# TUSB4041_PINOUT.net
KiCad netlist of a schematic drawn in Altium Designer
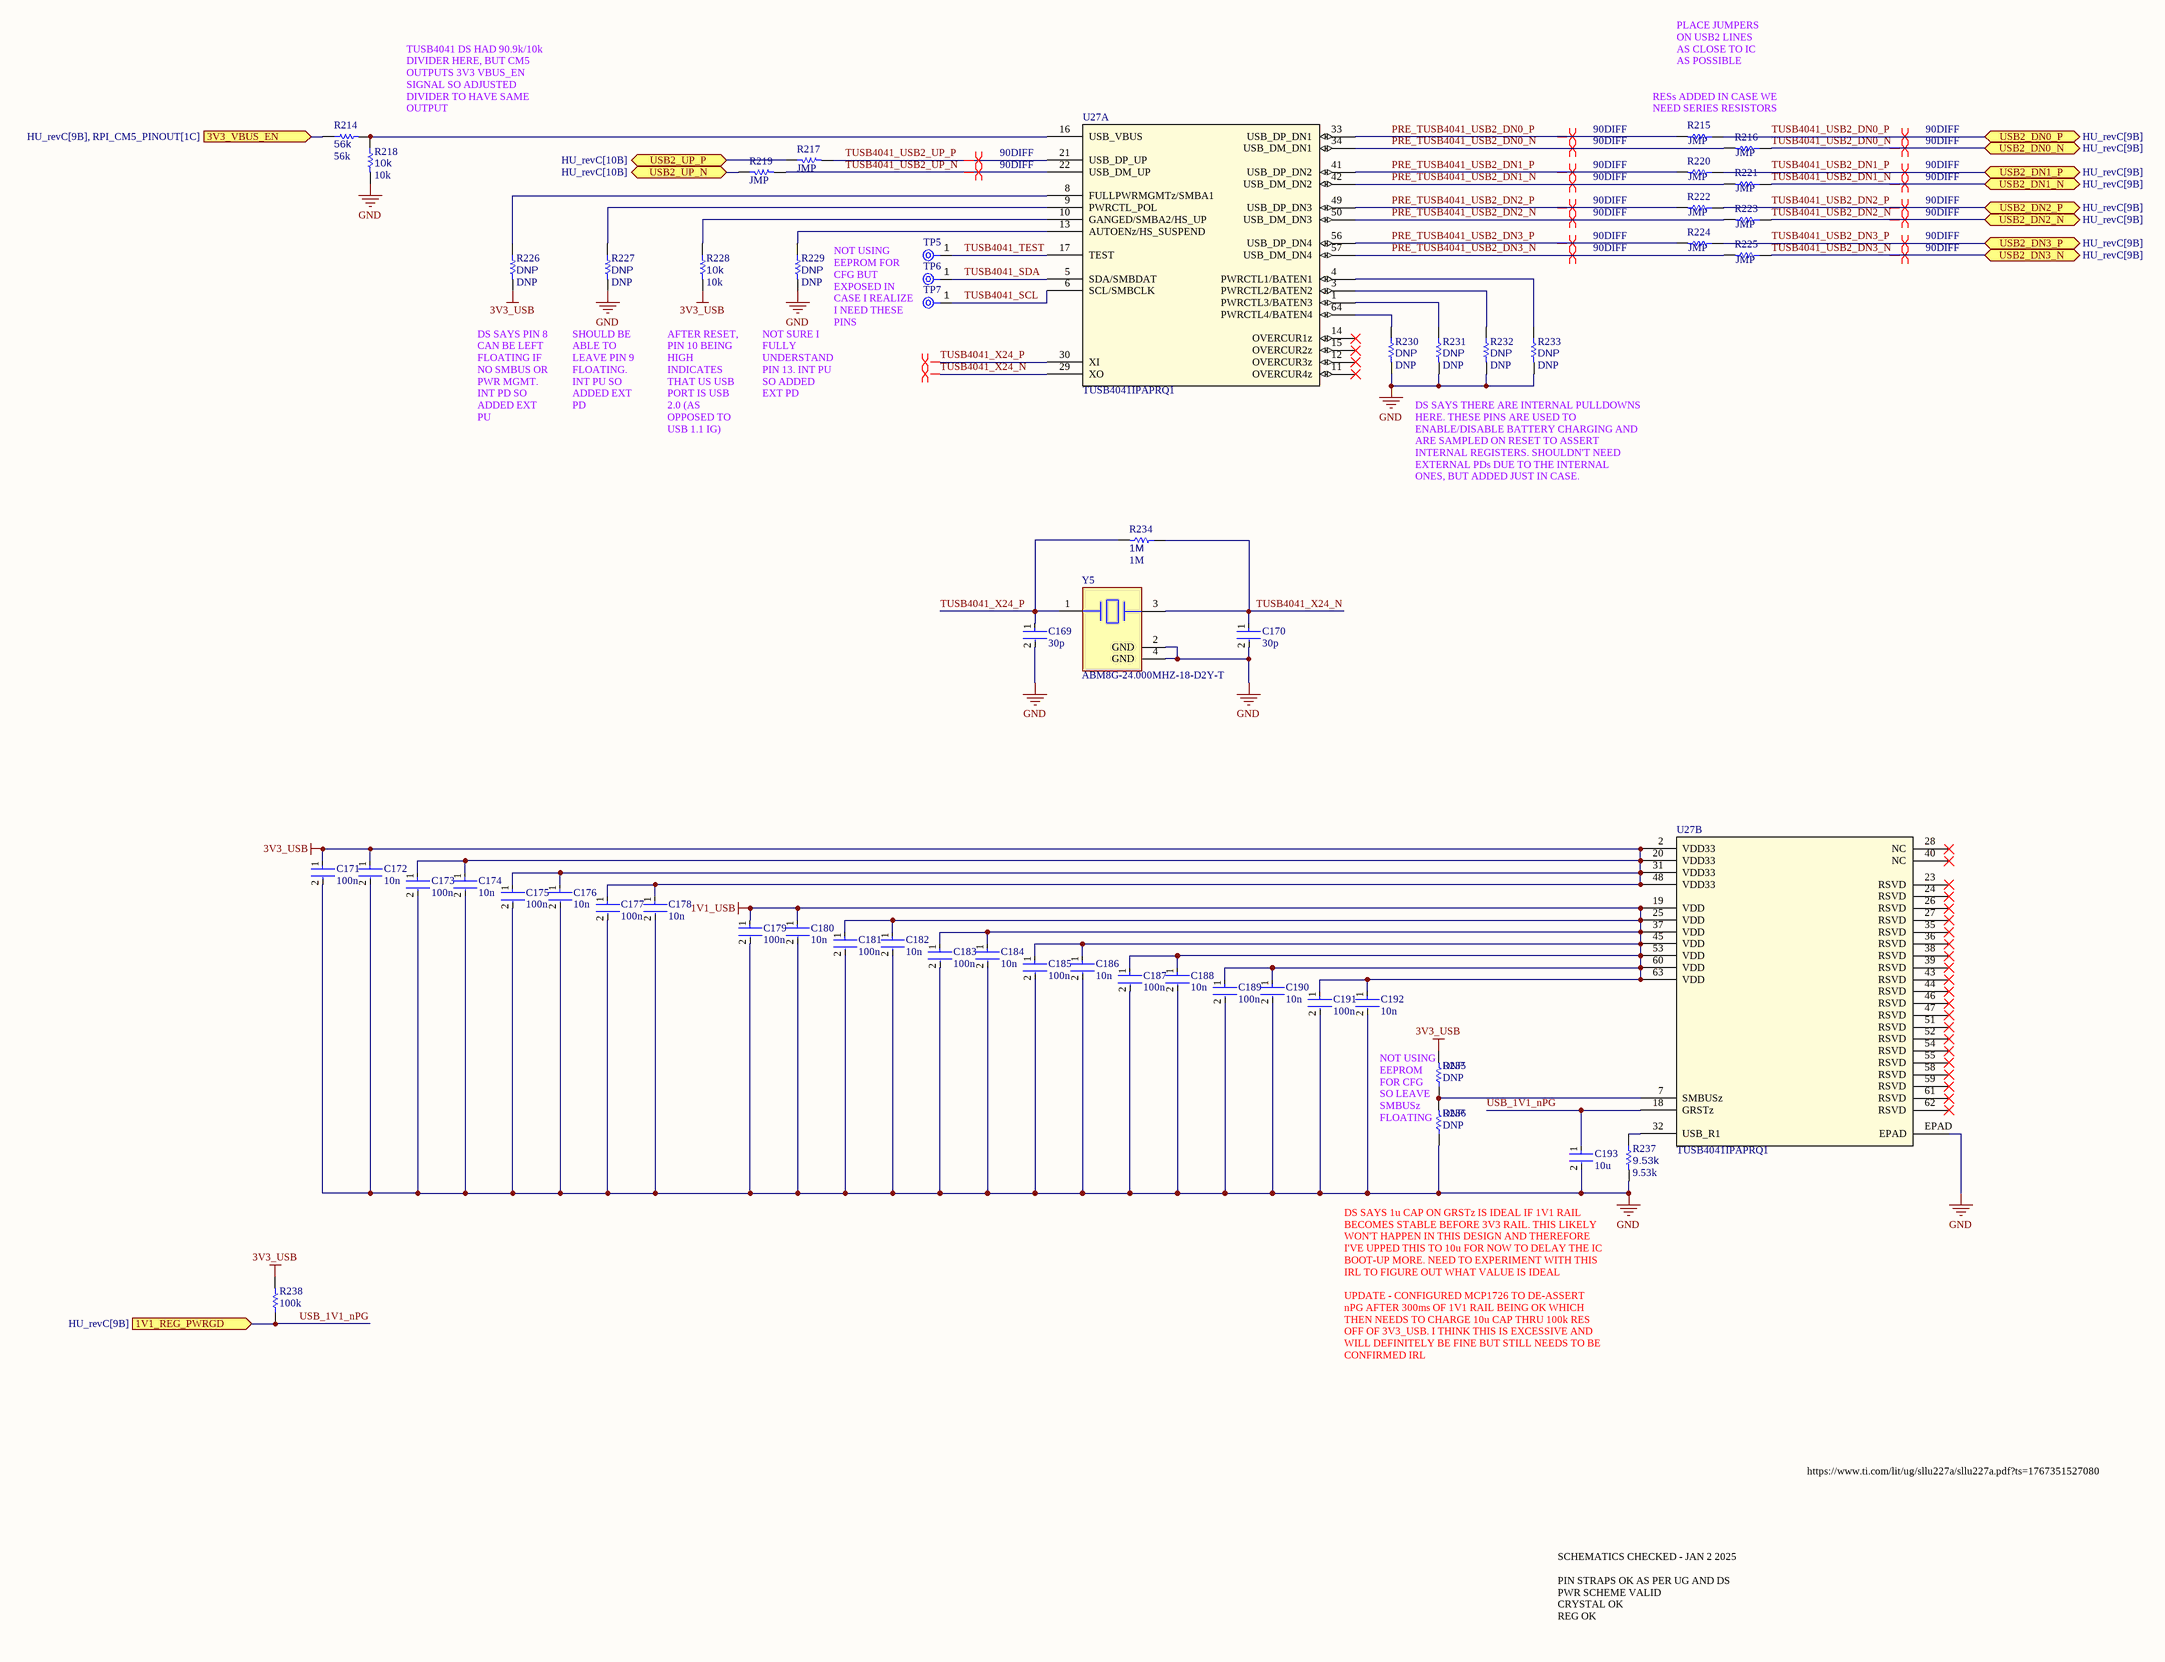
[diagram p0: TUSB4041_PINOUT.SchDoc]

(export (version "E")
  (design (tool "Eeschema 10.0.6"))
  (components
    (comp (ref "C169")
      (value "30p")
      (footprint "FP-0402-L_1_0_0_05-W_0_5-IPC_A")
      (description "LARGE PADS, 0402 CAP, CHANGE COMMENT TO MATCH REAL P/N")
      (libsource (lib "Space Concordia") (part "b4654b650e69147ec39a6b967a45e02"))
    )
    (comp (ref "C170")
      (value "30p")
      (footprint "FP-0402-L_1_0_0_05-W_0_5-IPC_A")
      (description "LARGE PADS, 0402 CAP, CHANGE COMMENT TO MATCH REAL P/N")
      (libsource (lib "Space Concordia") (part "b4654b650e69147ec39a6b967a45e02"))
    )
    (comp (ref "C171")
      (value "100n")
      (footprint "FP-0402-L_1_0_0_05-W_0_5-IPC_A")
      (description "LARGE PADS, 0402 CAP, CHANGE COMMENT TO MATCH REAL P/N")
      (libsource (lib "Space Concordia") (part "b4654b650e69147ec39a6b967a45e02"))
    )
    (comp (ref "C172")
      (value "10n")
      (footprint "FP-0402-L_1_0_0_05-W_0_5-IPC_A")
      (description "LARGE PADS, 0402 CAP, CHANGE COMMENT TO MATCH REAL P/N")
      (libsource (lib "Space Concordia") (part "b4654b650e69147ec39a6b967a45e02"))
    )
    (comp (ref "C173")
      (value "100n")
      (footprint "FP-0402-L_1_0_0_05-W_0_5-IPC_A")
      (description "LARGE PADS, 0402 CAP, CHANGE COMMENT TO MATCH REAL P/N")
      (libsource (lib "Space Concordia") (part "b4654b650e69147ec39a6b967a45e02"))
    )
    (comp (ref "C174")
      (value "10n")
      (footprint "FP-0402-L_1_0_0_05-W_0_5-IPC_A")
      (description "LARGE PADS, 0402 CAP, CHANGE COMMENT TO MATCH REAL P/N")
      (libsource (lib "Space Concordia") (part "b4654b650e69147ec39a6b967a45e02"))
    )
    (comp (ref "C175")
      (value "100n")
      (footprint "FP-0402-L_1_0_0_05-W_0_5-IPC_A")
      (description "LARGE PADS, 0402 CAP, CHANGE COMMENT TO MATCH REAL P/N")
      (libsource (lib "Space Concordia") (part "b4654b650e69147ec39a6b967a45e02"))
    )
    (comp (ref "C176")
      (value "10n")
      (footprint "FP-0402-L_1_0_0_05-W_0_5-IPC_A")
      (description "LARGE PADS, 0402 CAP, CHANGE COMMENT TO MATCH REAL P/N")
      (libsource (lib "Space Concordia") (part "b4654b650e69147ec39a6b967a45e02"))
    )
    (comp (ref "C177")
      (value "100n")
      (footprint "FP-0402-L_1_0_0_05-W_0_5-IPC_A")
      (description "LARGE PADS, 0402 CAP, CHANGE COMMENT TO MATCH REAL P/N")
      (libsource (lib "Space Concordia") (part "b4654b650e69147ec39a6b967a45e02"))
    )
    (comp (ref "C178")
      (value "10n")
      (footprint "FP-0402-L_1_0_0_05-W_0_5-IPC_A")
      (description "LARGE PADS, 0402 CAP, CHANGE COMMENT TO MATCH REAL P/N")
      (libsource (lib "Space Concordia") (part "b4654b650e69147ec39a6b967a45e02"))
    )
    (comp (ref "C179")
      (value "100n")
      (footprint "FP-0402-L_1_0_0_05-W_0_5-IPC_A")
      (description "LARGE PADS, 0402 CAP, CHANGE COMMENT TO MATCH REAL P/N")
      (libsource (lib "Space Concordia") (part "b4654b650e69147ec39a6b967a45e02"))
    )
    (comp (ref "C180")
      (value "10n")
      (footprint "FP-0402-L_1_0_0_05-W_0_5-IPC_A")
      (description "LARGE PADS, 0402 CAP, CHANGE COMMENT TO MATCH REAL P/N")
      (libsource (lib "Space Concordia") (part "b4654b650e69147ec39a6b967a45e02"))
    )
    (comp (ref "C181")
      (value "100n")
      (footprint "FP-0402-L_1_0_0_05-W_0_5-IPC_A")
      (description "LARGE PADS, 0402 CAP, CHANGE COMMENT TO MATCH REAL P/N")
      (libsource (lib "Space Concordia") (part "b4654b650e69147ec39a6b967a45e02"))
    )
    (comp (ref "C182")
      (value "10n")
      (footprint "FP-0402-L_1_0_0_05-W_0_5-IPC_A")
      (description "LARGE PADS, 0402 CAP, CHANGE COMMENT TO MATCH REAL P/N")
      (libsource (lib "Space Concordia") (part "b4654b650e69147ec39a6b967a45e02"))
    )
    (comp (ref "C183")
      (value "100n")
      (footprint "FP-0402-L_1_0_0_05-W_0_5-IPC_A")
      (description "LARGE PADS, 0402 CAP, CHANGE COMMENT TO MATCH REAL P/N")
      (libsource (lib "Space Concordia") (part "b4654b650e69147ec39a6b967a45e02"))
    )
    (comp (ref "C184")
      (value "10n")
      (footprint "FP-0402-L_1_0_0_05-W_0_5-IPC_A")
      (description "LARGE PADS, 0402 CAP, CHANGE COMMENT TO MATCH REAL P/N")
      (libsource (lib "Space Concordia") (part "b4654b650e69147ec39a6b967a45e02"))
    )
    (comp (ref "C185")
      (value "100n")
      (footprint "FP-0402-L_1_0_0_05-W_0_5-IPC_A")
      (description "LARGE PADS, 0402 CAP, CHANGE COMMENT TO MATCH REAL P/N")
      (libsource (lib "Space Concordia") (part "b4654b650e69147ec39a6b967a45e02"))
    )
    (comp (ref "C186")
      (value "10n")
      (footprint "FP-0402-L_1_0_0_05-W_0_5-IPC_A")
      (description "LARGE PADS, 0402 CAP, CHANGE COMMENT TO MATCH REAL P/N")
      (libsource (lib "Space Concordia") (part "b4654b650e69147ec39a6b967a45e02"))
    )
    (comp (ref "C187")
      (value "100n")
      (footprint "FP-0402-L_1_0_0_05-W_0_5-IPC_A")
      (description "LARGE PADS, 0402 CAP, CHANGE COMMENT TO MATCH REAL P/N")
      (libsource (lib "Space Concordia") (part "b4654b650e69147ec39a6b967a45e02"))
    )
    (comp (ref "C188")
      (value "10n")
      (footprint "FP-0402-L_1_0_0_05-W_0_5-IPC_A")
      (description "LARGE PADS, 0402 CAP, CHANGE COMMENT TO MATCH REAL P/N")
      (libsource (lib "Space Concordia") (part "b4654b650e69147ec39a6b967a45e02"))
    )
    (comp (ref "C189")
      (value "100n")
      (footprint "FP-0402-L_1_0_0_05-W_0_5-IPC_A")
      (description "LARGE PADS, 0402 CAP, CHANGE COMMENT TO MATCH REAL P/N")
      (libsource (lib "Space Concordia") (part "b4654b650e69147ec39a6b967a45e02"))
    )
    (comp (ref "C190")
      (value "10n")
      (footprint "FP-0402-L_1_0_0_05-W_0_5-IPC_A")
      (description "LARGE PADS, 0402 CAP, CHANGE COMMENT TO MATCH REAL P/N")
      (libsource (lib "Space Concordia") (part "b4654b650e69147ec39a6b967a45e02"))
    )
    (comp (ref "C191")
      (value "100n")
      (footprint "FP-0402-L_1_0_0_05-W_0_5-IPC_A")
      (description "LARGE PADS, 0402 CAP, CHANGE COMMENT TO MATCH REAL P/N")
      (libsource (lib "Space Concordia") (part "b4654b650e69147ec39a6b967a45e02"))
    )
    (comp (ref "C192")
      (value "10n")
      (footprint "FP-0402-L_1_0_0_05-W_0_5-IPC_A")
      (description "LARGE PADS, 0402 CAP, CHANGE COMMENT TO MATCH REAL P/N")
      (libsource (lib "Space Concordia") (part "b4654b650e69147ec39a6b967a45e02"))
    )
    (comp (ref "C193")
      (value "10u")
      (footprint "FP-0402-L_1_0_0_05-W_0_5-IPC_A")
      (description "LARGE PADS, 0402 CAP, CHANGE COMMENT TO MATCH REAL P/N")
      (libsource (lib "Space Concordia") (part "b4654b650e69147ec39a6b967a45e02"))
    )
    (comp (ref "R214")
      (value "56k")
      (footprint "R0603B")
      (description "Resistor")
      (fields (field (name "ALTIUM_VALUE") "56k"))
      (libsource (lib "Space Concordia") (part "Resistor"))
    )
    (comp (ref "R215")
      (value "JMP")
      (footprint "R0603B")
      (description "Resistor")
      (libsource (lib "Space Concordia") (part "Resistor"))
    )
    (comp (ref "R216")
      (value "JMP")
      (footprint "R0603B")
      (description "Resistor")
      (libsource (lib "Space Concordia") (part "Resistor"))
    )
    (comp (ref "R217")
      (value "JMP")
      (footprint "R0603B")
      (description "Resistor")
      (libsource (lib "Space Concordia") (part "Resistor"))
    )
    (comp (ref "R218")
      (value "10k")
      (footprint "R0603B")
      (description "Resistor")
      (fields (field (name "ALTIUM_VALUE") "10k"))
      (libsource (lib "Space Concordia") (part "Resistor"))
    )
    (comp (ref "R219")
      (value "JMP")
      (footprint "R0603B")
      (description "Resistor")
      (libsource (lib "Space Concordia") (part "Resistor"))
    )
    (comp (ref "R220")
      (value "JMP")
      (footprint "R0603B")
      (description "Resistor")
      (libsource (lib "Space Concordia") (part "Resistor"))
    )
    (comp (ref "R221")
      (value "JMP")
      (footprint "R0603B")
      (description "Resistor")
      (libsource (lib "Space Concordia") (part "Resistor"))
    )
    (comp (ref "R222")
      (value "JMP")
      (footprint "R0603B")
      (description "Resistor")
      (libsource (lib "Space Concordia") (part "Resistor"))
    )
    (comp (ref "R223")
      (value "JMP")
      (footprint "R0603B")
      (description "Resistor")
      (libsource (lib "Space Concordia") (part "Resistor"))
    )
    (comp (ref "R224")
      (value "JMP")
      (footprint "R0603B")
      (description "Resistor")
      (libsource (lib "Space Concordia") (part "Resistor"))
    )
    (comp (ref "R225")
      (value "JMP")
      (footprint "R0603B")
      (description "Resistor")
      (libsource (lib "Space Concordia") (part "Resistor"))
    )
    (comp (ref "R226")
      (value "DNP")
      (footprint "R0603B")
      (description "Resistor")
      (fields (field (name "ALTIUM_VALUE") "DNP"))
      (libsource (lib "Space Concordia") (part "Resistor"))
    )
    (comp (ref "R227")
      (value "DNP")
      (footprint "R0603B")
      (description "Resistor")
      (fields (field (name "ALTIUM_VALUE") "DNP"))
      (libsource (lib "Space Concordia") (part "Resistor"))
    )
    (comp (ref "R228")
      (value "10k")
      (footprint "R0603B")
      (description "Resistor")
      (fields (field (name "ALTIUM_VALUE") "10k"))
      (libsource (lib "Space Concordia") (part "Resistor"))
    )
    (comp (ref "R229")
      (value "DNP")
      (footprint "R0603B")
      (description "Resistor")
      (fields (field (name "ALTIUM_VALUE") "DNP"))
      (libsource (lib "Space Concordia") (part "Resistor"))
    )
    (comp (ref "R230")
      (value "DNP")
      (footprint "R0603B")
      (description "Resistor")
      (fields (field (name "ALTIUM_VALUE") "DNP"))
      (libsource (lib "Space Concordia") (part "Resistor"))
    )
    (comp (ref "R231")
      (value "DNP")
      (footprint "R0603B")
      (description "Resistor")
      (fields (field (name "ALTIUM_VALUE") "DNP"))
      (libsource (lib "Space Concordia") (part "Resistor"))
    )
    (comp (ref "R232")
      (value "DNP")
      (footprint "R0603B")
      (description "Resistor")
      (fields (field (name "ALTIUM_VALUE") "DNP"))
      (libsource (lib "Space Concordia") (part "Resistor"))
    )
    (comp (ref "R233")
      (value "DNP")
      (footprint "R0603B")
      (description "Resistor")
      (fields (field (name "ALTIUM_VALUE") "DNP"))
      (libsource (lib "Space Concordia") (part "Resistor"))
    )
    (comp (ref "R234")
      (value "1M")
      (footprint "R0603B")
      (description "Resistor")
      (fields (field (name "ALTIUM_VALUE") "1M"))
      (libsource (lib "Space Concordia") (part "Resistor"))
    )
    (comp (ref "R235")
      (value "DNP")
      (footprint "R0603B")
      (description "Resistor")
      (fields (field (name "ALTIUM_VALUE") "DNP"))
      (libsource (lib "Space Concordia") (part "Resistor"))
    )
    (comp (ref "R236")
      (value "DNP")
      (footprint "R0603B")
      (description "Resistor")
      (fields (field (name "ALTIUM_VALUE") "DNP"))
      (libsource (lib "Space Concordia") (part "Resistor"))
    )
    (comp (ref "R237")
      (value "9.53k")
      (footprint "R0603B")
      (description "Resistor")
      (fields (field (name "ALTIUM_VALUE") "9.53k"))
      (libsource (lib "Space Concordia") (part "Resistor"))
    )
    (comp (ref "R238")
      (value "100k")
      (footprint "R0603B")
      (description "Resistor")
      (libsource (lib "Space Concordia") (part "Resistor"))
    )
    (comp (ref "TP5")
      (value "TPAD6R")
      (footprint "New footprint 1")
      (description "Test Point .6mm")
      (libsource (lib "Space Concordia") (part "TP"))
    )
    (comp (ref "TP6")
      (value "TPAD6R")
      (footprint "New footprint 1")
      (description "Test Point .6mm")
      (libsource (lib "Space Concordia") (part "TP"))
    )
    (comp (ref "TP7")
      (value "TPAD6R")
      (footprint "New footprint 1")
      (description "Test Point .6mm")
      (libsource (lib "Space Concordia") (part "TP"))
    )
    (comp (ref "U27")
      (value "TUSB4041IPAPRQ1")
      (footprint "TUSB4041IPAPRQ1-Footprint-1")
      (description "IC USB 2.0 4PORT HUB 64HTQFP USB Hub Controller USB 2.0 USB Interface 64-HTQFP (10x10)")
      (libsource (lib "Space Concordia") (part "TUSB4041IPAPRQ1"))
    )
    (comp (ref "Y5")
      (value "ABM8G-24.000MHZ-18-D2Y-T")
      (footprint "FP-ABM8G-MFG")
      (description "Crystal 24MHz ±20ppm (Tol) ±30ppm (Stability) 18pF FUND 60Ω 4-Pin SMD T/R")
      (fields (field (name "TOLERANCE") "20ppm"))
      (libsource (lib "Altium Content Vault") (part "48e526d86b7f2615d98721063c72f49"))
    )
  )
  (nets
    (net (code "1") (name "/3V3_VBUS_EN") (class "Default")
      (node (ref "R214") (pin "1") (pinfunction "1_1") (pintype "passive"))
    )
    (net (code "2") (name "/PRE_TUSB4041_USB2_DN0_N") (class "Default")
      (node (ref "R216") (pin "2") (pinfunction "2_2") (pintype "passive"))
      (node (ref "U27") (pin "34") (pinfunction "USB_DM_DN1_34") (pintype "bidirectional"))
    )
    (net (code "3") (name "/PRE_TUSB4041_USB2_DN0_P") (class "Default")
      (node (ref "R215") (pin "2") (pinfunction "2_2") (pintype "passive"))
      (node (ref "U27") (pin "33") (pinfunction "USB_DP_DN1_33") (pintype "bidirectional"))
    )
    (net (code "4") (name "/PRE_TUSB4041_USB2_DN1_N") (class "Default")
      (node (ref "R221") (pin "2") (pinfunction "2_2") (pintype "passive"))
      (node (ref "U27") (pin "42") (pinfunction "USB_DM_DN2_42") (pintype "bidirectional"))
    )
    (net (code "5") (name "/PRE_TUSB4041_USB2_DN1_P") (class "Default")
      (node (ref "R220") (pin "2") (pinfunction "2_2") (pintype "passive"))
      (node (ref "U27") (pin "41") (pinfunction "USB_DP_DN2_41") (pintype "bidirectional"))
    )
    (net (code "6") (name "/PRE_TUSB4041_USB2_DN2_N") (class "Default")
      (node (ref "R223") (pin "2") (pinfunction "2_2") (pintype "passive"))
      (node (ref "U27") (pin "50") (pinfunction "USB_DM_DN3_50") (pintype "bidirectional"))
    )
    (net (code "7") (name "/PRE_TUSB4041_USB2_DN2_P") (class "Default")
      (node (ref "R222") (pin "2") (pinfunction "2_2") (pintype "passive"))
      (node (ref "U27") (pin "49") (pinfunction "USB_DP_DN3_49") (pintype "bidirectional"))
    )
    (net (code "8") (name "/PRE_TUSB4041_USB2_DN3_N") (class "Default")
      (node (ref "R225") (pin "2") (pinfunction "2_2") (pintype "passive"))
      (node (ref "U27") (pin "57") (pinfunction "USB_DM_DN4_57") (pintype "bidirectional"))
    )
    (net (code "9") (name "/PRE_TUSB4041_USB2_DN3_P") (class "Default")
      (node (ref "R224") (pin "2") (pinfunction "2_2") (pintype "passive"))
      (node (ref "U27") (pin "56") (pinfunction "USB_DP_DN4_56") (pintype "bidirectional"))
    )
    (net (code "10") (name "/TUSB4041_SCL") (class "Default")
      (node (ref "TP7") (pin "1") (pinfunction "TP_1") (pintype "passive"))
      (node (ref "U27") (pin "6") (pinfunction "SCL/SMBCLK_6") (pintype "passive"))
    )
    (net (code "11") (name "/TUSB4041_SDA") (class "Default")
      (node (ref "TP6") (pin "1") (pinfunction "TP_1") (pintype "passive"))
      (node (ref "U27") (pin "5") (pinfunction "SDA/SMBDAT_5") (pintype "passive"))
    )
    (net (code "12") (name "/TUSB4041_TEST") (class "Default")
      (node (ref "TP5") (pin "1") (pinfunction "TP_1") (pintype "passive"))
      (node (ref "U27") (pin "17") (pinfunction "TEST_17") (pintype "passive"))
    )
    (net (code "13") (name "/TUSB4041_USB2_DN0_N") (class "Default")
      (node (ref "R216") (pin "1") (pinfunction "1_1") (pintype "passive"))
    )
    (net (code "14") (name "/TUSB4041_USB2_DN0_P") (class "Default")
      (node (ref "R215") (pin "1") (pinfunction "1_1") (pintype "passive"))
    )
    (net (code "15") (name "/TUSB4041_USB2_DN1_N") (class "Default")
      (node (ref "R221") (pin "1") (pinfunction "1_1") (pintype "passive"))
    )
    (net (code "16") (name "/TUSB4041_USB2_DN1_P") (class "Default")
      (node (ref "R220") (pin "1") (pinfunction "1_1") (pintype "passive"))
    )
    (net (code "17") (name "/TUSB4041_USB2_DN2_N") (class "Default")
      (node (ref "R223") (pin "1") (pinfunction "1_1") (pintype "passive"))
    )
    (net (code "18") (name "/TUSB4041_USB2_DN2_P") (class "Default")
      (node (ref "R222") (pin "1") (pinfunction "1_1") (pintype "passive"))
    )
    (net (code "19") (name "/TUSB4041_USB2_DN3_N") (class "Default")
      (node (ref "R225") (pin "1") (pinfunction "1_1") (pintype "passive"))
    )
    (net (code "20") (name "/TUSB4041_USB2_DN3_P") (class "Default")
      (node (ref "R224") (pin "1") (pinfunction "1_1") (pintype "passive"))
    )
    (net (code "21") (name "/TUSB4041_USB2_UP_N") (class "Default")
      (node (ref "R219") (pin "2") (pinfunction "2_2") (pintype "passive"))
      (node (ref "U27") (pin "22") (pinfunction "USB_DM_UP_22") (pintype "passive"))
    )
    (net (code "22") (name "/TUSB4041_USB2_UP_P") (class "Default")
      (node (ref "R217") (pin "2") (pinfunction "2_2") (pintype "passive"))
      (node (ref "U27") (pin "21") (pinfunction "USB_DP_UP_21") (pintype "passive"))
    )
    (net (code "23") (name "/TUSB4041_X24_N") (class "Default")
      (node (ref "C170") (pin "1") (pinfunction "1_1") (pintype "passive"))
      (node (ref "R234") (pin "1") (pinfunction "1_1") (pintype "passive"))
      (node (ref "U27") (pin "29") (pinfunction "XO_29") (pintype "passive"))
      (node (ref "Y5") (pin "3") (pinfunction "3_3") (pintype "passive"))
    )
    (net (code "24") (name "/TUSB4041_X24_P") (class "Default")
      (node (ref "C169") (pin "1") (pinfunction "1_1") (pintype "passive"))
      (node (ref "R234") (pin "2") (pinfunction "2_2") (pintype "passive"))
      (node (ref "U27") (pin "30") (pinfunction "XI_30") (pintype "passive"))
      (node (ref "Y5") (pin "1") (pinfunction "1_1") (pintype "passive"))
    )
    (net (code "25") (name "/USB2_UP_N") (class "Default")
      (node (ref "R219") (pin "1") (pinfunction "1_1") (pintype "passive"))
    )
    (net (code "26") (name "/USB2_UP_P") (class "Default")
      (node (ref "R217") (pin "1") (pinfunction "1_1") (pintype "passive"))
    )
    (net (code "27") (name "/USB_1V1_nPG") (class "Default")
      (node (ref "C193") (pin "1") (pinfunction "1_1") (pintype "passive"))
      (node (ref "R238") (pin "1") (pinfunction "1_1") (pintype "passive"))
      (node (ref "U27") (pin "18") (pinfunction "GRSTz_18") (pintype "passive"))
    )
    (net (code "28") (name "1V1_USB") (class "Default")
      (node (ref "C179") (pin "1") (pinfunction "1_1") (pintype "passive"))
      (node (ref "C180") (pin "1") (pinfunction "1_1") (pintype "passive"))
      (node (ref "C181") (pin "1") (pinfunction "1_1") (pintype "passive"))
      (node (ref "C182") (pin "1") (pinfunction "1_1") (pintype "passive"))
      (node (ref "C183") (pin "1") (pinfunction "1_1") (pintype "passive"))
      (node (ref "C184") (pin "1") (pinfunction "1_1") (pintype "passive"))
      (node (ref "C185") (pin "1") (pinfunction "1_1") (pintype "passive"))
      (node (ref "C186") (pin "1") (pinfunction "1_1") (pintype "passive"))
      (node (ref "C187") (pin "1") (pinfunction "1_1") (pintype "passive"))
      (node (ref "C188") (pin "1") (pinfunction "1_1") (pintype "passive"))
      (node (ref "C189") (pin "1") (pinfunction "1_1") (pintype "passive"))
      (node (ref "C190") (pin "1") (pinfunction "1_1") (pintype "passive"))
      (node (ref "C191") (pin "1") (pinfunction "1_1") (pintype "passive"))
      (node (ref "C192") (pin "1") (pinfunction "1_1") (pintype "passive"))
      (node (ref "U27") (pin "19") (pinfunction "VDD_19") (pintype "power_in"))
      (node (ref "U27") (pin "25") (pinfunction "VDD_25") (pintype "power_in"))
      (node (ref "U27") (pin "37") (pinfunction "VDD_37") (pintype "power_in"))
      (node (ref "U27") (pin "45") (pinfunction "VDD_45") (pintype "power_in"))
      (node (ref "U27") (pin "53") (pinfunction "VDD_53") (pintype "power_in"))
      (node (ref "U27") (pin "60") (pinfunction "VDD_60") (pintype "power_in"))
      (node (ref "U27") (pin "63") (pinfunction "VDD_63") (pintype "power_in"))
    )
    (net (code "29") (name "3V3_USB") (class "Default")
      (node (ref "C171") (pin "1") (pinfunction "1_1") (pintype "passive"))
      (node (ref "C172") (pin "1") (pinfunction "1_1") (pintype "passive"))
      (node (ref "C173") (pin "1") (pinfunction "1_1") (pintype "passive"))
      (node (ref "C174") (pin "1") (pinfunction "1_1") (pintype "passive"))
      (node (ref "C175") (pin "1") (pinfunction "1_1") (pintype "passive"))
      (node (ref "C176") (pin "1") (pinfunction "1_1") (pintype "passive"))
      (node (ref "C177") (pin "1") (pinfunction "1_1") (pintype "passive"))
      (node (ref "C178") (pin "1") (pinfunction "1_1") (pintype "passive"))
      (node (ref "R226") (pin "2") (pinfunction "2_2") (pintype "passive"))
      (node (ref "R228") (pin "2") (pinfunction "2_2") (pintype "passive"))
      (node (ref "R235") (pin "2") (pinfunction "2_2") (pintype "passive"))
      (node (ref "R238") (pin "2") (pinfunction "2_2") (pintype "passive"))
      (node (ref "U27") (pin "2") (pinfunction "VDD33_2") (pintype "power_in"))
      (node (ref "U27") (pin "20") (pinfunction "VDD33_20") (pintype "power_in"))
      (node (ref "U27") (pin "31") (pinfunction "VDD33_31") (pintype "power_in"))
      (node (ref "U27") (pin "48") (pinfunction "VDD33_48") (pintype "power_in"))
    )
    (net (code "30") (name "GND") (class "Default")
      (node (ref "C169") (pin "2") (pinfunction "2_2") (pintype "passive"))
      (node (ref "C170") (pin "2") (pinfunction "2_2") (pintype "passive"))
      (node (ref "C171") (pin "2") (pinfunction "2_2") (pintype "passive"))
      (node (ref "C172") (pin "2") (pinfunction "2_2") (pintype "passive"))
      (node (ref "C173") (pin "2") (pinfunction "2_2") (pintype "passive"))
      (node (ref "C174") (pin "2") (pinfunction "2_2") (pintype "passive"))
      (node (ref "C175") (pin "2") (pinfunction "2_2") (pintype "passive"))
      (node (ref "C176") (pin "2") (pinfunction "2_2") (pintype "passive"))
      (node (ref "C177") (pin "2") (pinfunction "2_2") (pintype "passive"))
      (node (ref "C178") (pin "2") (pinfunction "2_2") (pintype "passive"))
      (node (ref "C179") (pin "2") (pinfunction "2_2") (pintype "passive"))
      (node (ref "C180") (pin "2") (pinfunction "2_2") (pintype "passive"))
      (node (ref "C181") (pin "2") (pinfunction "2_2") (pintype "passive"))
      (node (ref "C182") (pin "2") (pinfunction "2_2") (pintype "passive"))
      (node (ref "C183") (pin "2") (pinfunction "2_2") (pintype "passive"))
      (node (ref "C184") (pin "2") (pinfunction "2_2") (pintype "passive"))
      (node (ref "C185") (pin "2") (pinfunction "2_2") (pintype "passive"))
      (node (ref "C186") (pin "2") (pinfunction "2_2") (pintype "passive"))
      (node (ref "C187") (pin "2") (pinfunction "2_2") (pintype "passive"))
      (node (ref "C188") (pin "2") (pinfunction "2_2") (pintype "passive"))
      (node (ref "C189") (pin "2") (pinfunction "2_2") (pintype "passive"))
      (node (ref "C190") (pin "2") (pinfunction "2_2") (pintype "passive"))
      (node (ref "C191") (pin "2") (pinfunction "2_2") (pintype "passive"))
      (node (ref "C192") (pin "2") (pinfunction "2_2") (pintype "passive"))
      (node (ref "C193") (pin "2") (pinfunction "2_2") (pintype "passive"))
      (node (ref "R218") (pin "2") (pinfunction "2_2") (pintype "passive"))
      (node (ref "R227") (pin "2") (pinfunction "2_2") (pintype "passive"))
      (node (ref "R229") (pin "2") (pinfunction "2_2") (pintype "passive"))
      (node (ref "R230") (pin "2") (pinfunction "2_2") (pintype "passive"))
      (node (ref "R231") (pin "2") (pinfunction "2_2") (pintype "passive"))
      (node (ref "R232") (pin "2") (pinfunction "2_2") (pintype "passive"))
      (node (ref "R233") (pin "2") (pinfunction "2_2") (pintype "passive"))
      (node (ref "R236") (pin "1") (pinfunction "1_1") (pintype "passive"))
      (node (ref "R237") (pin "2") (pinfunction "2_2") (pintype "passive"))
      (node (ref "U27") (pin "EPAD") (pinfunction "EPAD_EPAD") (pintype "passive"))
      (node (ref "Y5") (pin "2") (pinfunction "GND_2") (pintype "power_in"))
      (node (ref "Y5") (pin "4") (pinfunction "GND_4") (pintype "power_in"))
    )
    (net (code "31") (name "Net-(U27A-AUTOENz{slash}HS_SUSPEND)") (class "Default")
      (node (ref "R229") (pin "1") (pinfunction "1_1") (pintype "passive"))
      (node (ref "U27") (pin "13") (pinfunction "AUTOENz/HS_SUSPEND_13") (pintype "passive"))
    )
    (net (code "32") (name "Net-(U27A-FULLPWRMGMTz{slash}SMBA1)") (class "Default")
      (node (ref "R226") (pin "1") (pinfunction "1_1") (pintype "passive"))
      (node (ref "U27") (pin "8") (pinfunction "FULLPWRMGMTz/SMBA1_8") (pintype "passive"))
    )
    (net (code "33") (name "Net-(U27A-GANGED{slash}SMBA2{slash}HS_UP)") (class "Default")
      (node (ref "R228") (pin "1") (pinfunction "1_1") (pintype "passive"))
      (node (ref "U27") (pin "10") (pinfunction "GANGED/SMBA2/HS_UP_10") (pintype "passive"))
    )
    (net (code "34") (name "Net-(U27A-PWRCTL1{slash}BATEN1)") (class "Default")
      (node (ref "R233") (pin "1") (pinfunction "1_1") (pintype "passive"))
      (node (ref "U27") (pin "4") (pinfunction "PWRCTL1/BATEN1_4") (pintype "bidirectional"))
    )
    (net (code "35") (name "Net-(U27A-PWRCTL2{slash}BATEN2)") (class "Default")
      (node (ref "R232") (pin "1") (pinfunction "1_1") (pintype "passive"))
      (node (ref "U27") (pin "3") (pinfunction "PWRCTL2/BATEN2_3") (pintype "bidirectional"))
    )
    (net (code "36") (name "Net-(U27A-PWRCTL3{slash}BATEN3)") (class "Default")
      (node (ref "R231") (pin "1") (pinfunction "1_1") (pintype "passive"))
      (node (ref "U27") (pin "1") (pinfunction "PWRCTL3/BATEN3_1") (pintype "bidirectional"))
    )
    (net (code "37") (name "Net-(U27A-PWRCTL4{slash}BATEN4)") (class "Default")
      (node (ref "R230") (pin "1") (pinfunction "1_1") (pintype "passive"))
      (node (ref "U27") (pin "64") (pinfunction "PWRCTL4/BATEN4_64") (pintype "bidirectional"))
    )
    (net (code "38") (name "Net-(U27A-PWRCTL_POL)") (class "Default")
      (node (ref "R227") (pin "1") (pinfunction "1_1") (pintype "passive"))
      (node (ref "U27") (pin "9") (pinfunction "PWRCTL_POL_9") (pintype "passive"))
    )
    (net (code "39") (name "Net-(U27A-USB_VBUS)") (class "Default")
      (node (ref "R214") (pin "2") (pinfunction "2_2") (pintype "passive"))
      (node (ref "R218") (pin "1") (pinfunction "1_1") (pintype "passive"))
      (node (ref "U27") (pin "16") (pinfunction "USB_VBUS_16") (pintype "passive"))
    )
    (net (code "40") (name "Net-(U27B-SMBUSz)") (class "Default")
      (node (ref "R235") (pin "1") (pinfunction "1_1") (pintype "passive"))
      (node (ref "R236") (pin "2") (pinfunction "2_2") (pintype "passive"))
      (node (ref "U27") (pin "7") (pinfunction "SMBUSz_7") (pintype "passive"))
    )
    (net (code "41") (name "Net-(U27B-USB_R1)") (class "Default")
      (node (ref "R237") (pin "1") (pinfunction "1_1") (pintype "passive"))
      (node (ref "U27") (pin "32") (pinfunction "USB_R1_32") (pintype "passive"))
    )
    (net (code "42") (name "unconnected-(U27A-OVERCUR1z-Pad14)") (class "Default")
      (node (ref "U27") (pin "14") (pinfunction "OVERCUR1z_14") (pintype "bidirectional+no_connect"))
    )
    (net (code "43") (name "unconnected-(U27A-OVERCUR2z-Pad15)") (class "Default")
      (node (ref "U27") (pin "15") (pinfunction "OVERCUR2z_15") (pintype "bidirectional+no_connect"))
    )
    (net (code "44") (name "unconnected-(U27A-OVERCUR3z-Pad12)") (class "Default")
      (node (ref "U27") (pin "12") (pinfunction "OVERCUR3z_12") (pintype "bidirectional+no_connect"))
    )
    (net (code "45") (name "unconnected-(U27A-OVERCUR4z-Pad11)") (class "Default")
      (node (ref "U27") (pin "11") (pinfunction "OVERCUR4z_11") (pintype "bidirectional+no_connect"))
    )
    (net (code "46") (name "unconnected-(U27B-NC-Pad28)") (class "Default")
      (node (ref "U27") (pin "28") (pinfunction "NC_28") (pintype "passive+no_connect"))
    )
    (net (code "47") (name "unconnected-(U27B-NC-Pad40)") (class "Default")
      (node (ref "U27") (pin "40") (pinfunction "NC_40") (pintype "passive+no_connect"))
    )
    (net (code "48") (name "unconnected-(U27B-RSVD-Pad23)") (class "Default")
      (node (ref "U27") (pin "23") (pinfunction "RSVD_23") (pintype "passive+no_connect"))
    )
    (net (code "49") (name "unconnected-(U27B-RSVD-Pad24)") (class "Default")
      (node (ref "U27") (pin "24") (pinfunction "RSVD_24") (pintype "passive+no_connect"))
    )
    (net (code "50") (name "unconnected-(U27B-RSVD-Pad26)") (class "Default")
      (node (ref "U27") (pin "26") (pinfunction "RSVD_26") (pintype "passive+no_connect"))
    )
    (net (code "51") (name "unconnected-(U27B-RSVD-Pad27)") (class "Default")
      (node (ref "U27") (pin "27") (pinfunction "RSVD_27") (pintype "passive+no_connect"))
    )
    (net (code "52") (name "unconnected-(U27B-RSVD-Pad35)") (class "Default")
      (node (ref "U27") (pin "35") (pinfunction "RSVD_35") (pintype "passive+no_connect"))
    )
    (net (code "53") (name "unconnected-(U27B-RSVD-Pad36)") (class "Default")
      (node (ref "U27") (pin "36") (pinfunction "RSVD_36") (pintype "passive+no_connect"))
    )
    (net (code "54") (name "unconnected-(U27B-RSVD-Pad38)") (class "Default")
      (node (ref "U27") (pin "38") (pinfunction "RSVD_38") (pintype "passive+no_connect"))
    )
    (net (code "55") (name "unconnected-(U27B-RSVD-Pad39)") (class "Default")
      (node (ref "U27") (pin "39") (pinfunction "RSVD_39") (pintype "passive+no_connect"))
    )
    (net (code "56") (name "unconnected-(U27B-RSVD-Pad43)") (class "Default")
      (node (ref "U27") (pin "43") (pinfunction "RSVD_43") (pintype "passive+no_connect"))
    )
    (net (code "57") (name "unconnected-(U27B-RSVD-Pad44)") (class "Default")
      (node (ref "U27") (pin "44") (pinfunction "RSVD_44") (pintype "passive+no_connect"))
    )
    (net (code "58") (name "unconnected-(U27B-RSVD-Pad46)") (class "Default")
      (node (ref "U27") (pin "46") (pinfunction "RSVD_46") (pintype "passive+no_connect"))
    )
    (net (code "59") (name "unconnected-(U27B-RSVD-Pad47)") (class "Default")
      (node (ref "U27") (pin "47") (pinfunction "RSVD_47") (pintype "passive+no_connect"))
    )
    (net (code "60") (name "unconnected-(U27B-RSVD-Pad51)") (class "Default")
      (node (ref "U27") (pin "51") (pinfunction "RSVD_51") (pintype "passive+no_connect"))
    )
    (net (code "61") (name "unconnected-(U27B-RSVD-Pad52)") (class "Default")
      (node (ref "U27") (pin "52") (pinfunction "RSVD_52") (pintype "passive+no_connect"))
    )
    (net (code "62") (name "unconnected-(U27B-RSVD-Pad54)") (class "Default")
      (node (ref "U27") (pin "54") (pinfunction "RSVD_54") (pintype "passive+no_connect"))
    )
    (net (code "63") (name "unconnected-(U27B-RSVD-Pad55)") (class "Default")
      (node (ref "U27") (pin "55") (pinfunction "RSVD_55") (pintype "passive+no_connect"))
    )
    (net (code "64") (name "unconnected-(U27B-RSVD-Pad58)") (class "Default")
      (node (ref "U27") (pin "58") (pinfunction "RSVD_58") (pintype "passive+no_connect"))
    )
    (net (code "65") (name "unconnected-(U27B-RSVD-Pad59)") (class "Default")
      (node (ref "U27") (pin "59") (pinfunction "RSVD_59") (pintype "passive+no_connect"))
    )
    (net (code "66") (name "unconnected-(U27B-RSVD-Pad61)") (class "Default")
      (node (ref "U27") (pin "61") (pinfunction "RSVD_61") (pintype "passive+no_connect"))
    )
    (net (code "67") (name "unconnected-(U27B-RSVD-Pad62)") (class "Default")
      (node (ref "U27") (pin "62") (pinfunction "RSVD_62") (pintype "passive+no_connect"))
    )
  )
)
